# USB2_0_Connector.net
KiCad netlist of a schematic drawn in Altium Designer
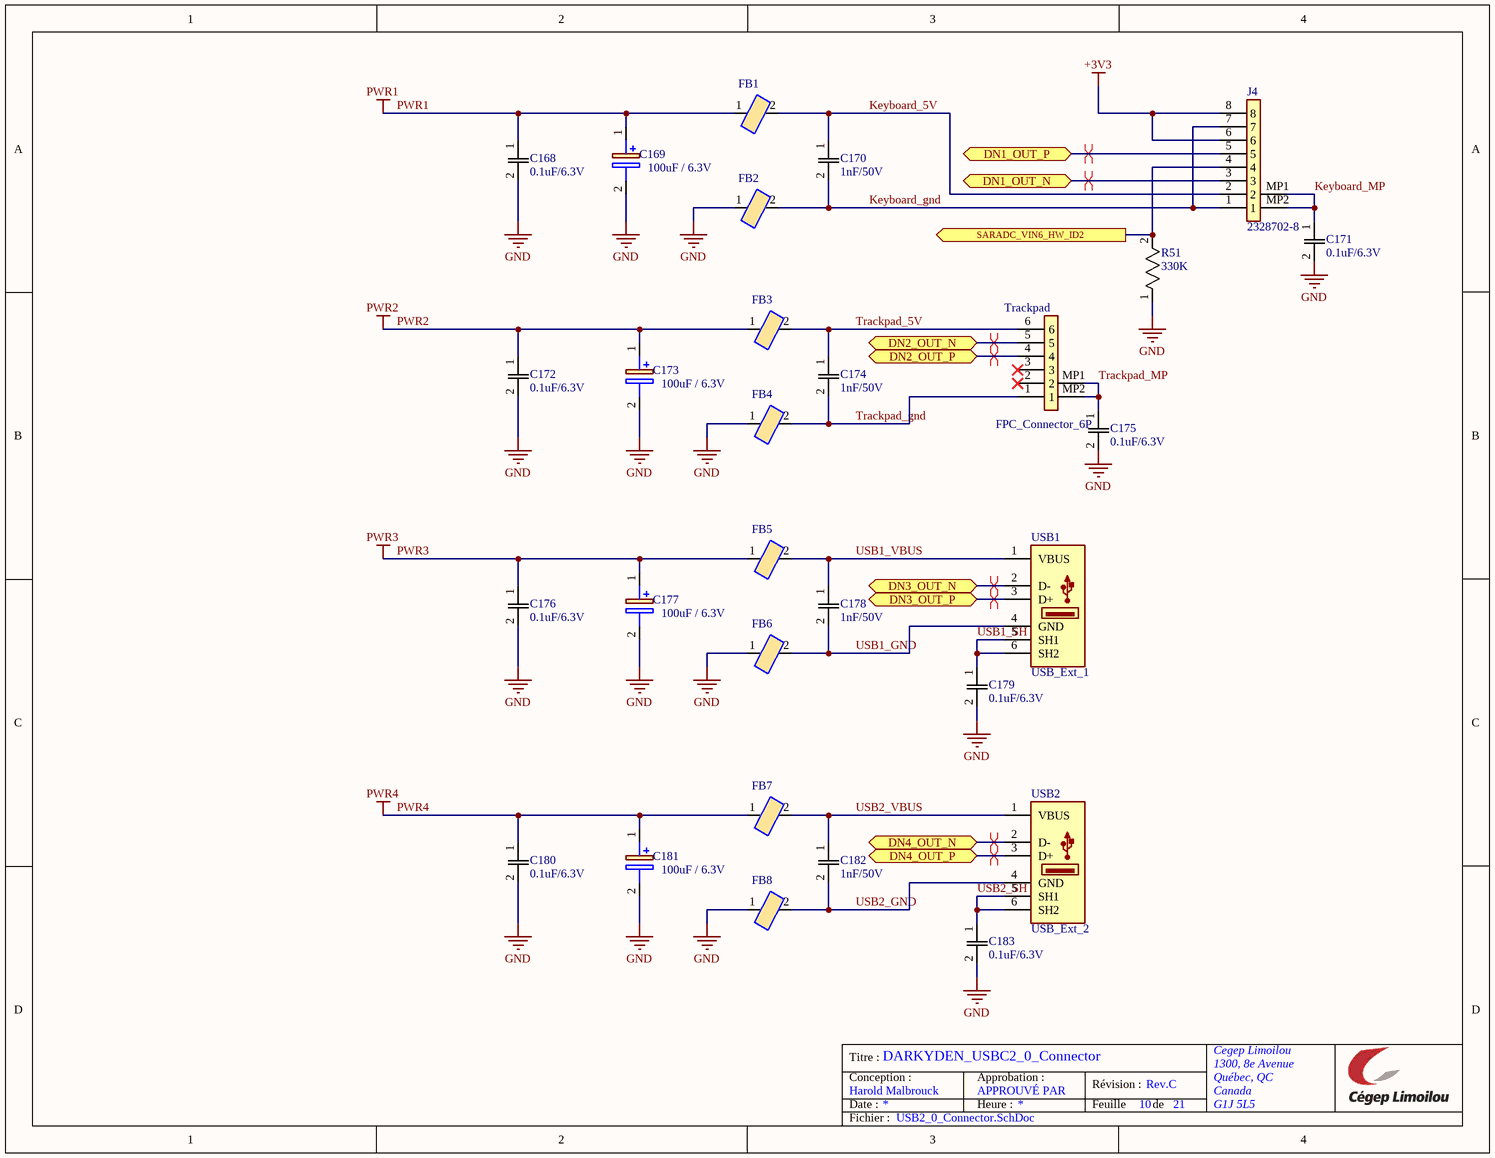
[diagram p0: USB2_0_Connector.SchDoc]

(export (version "E")
  (design (tool "Eeschema 10.0.6"))
  (components
    (comp (ref "C168")
      (value "0.1uF/6.3V")
      (footprint "C0805")
      (description "0.1uF 6.3V X7R 10% Pad SMD 0805 125C T/R")
      (fields
        (field (name "MOUSER PART NUMBER") "80-C0805C104K9R")
        (field (name "ARROW PART NUMBER") "C0805C104K9RACTU")
      )
      (libsource (lib "DARKYDEN") (part "C0805C104K9RACTU"))
    )
    (comp (ref "C169")
      (value "100uF / 6.3V")
      (footprint "SamacSys:EEE0GA101SR")
      (description "100uF 6.3V 20% Cap Aluminum Lytic  SMD 0.36 Ohm 240mA 2000h 105C Automotive T/R")
      (fields
        (field (name "MOUSER PART NUMBER") "667-EEE-FPJ101UAR")
        (field (name "ARROW PART NUMBER") "EEE-FPJ101UAR")
      )
      (libsource (lib "SamacSys") (part "EEE-FPJ101UAR"))
    )
    (comp (ref "C170")
      (value "1nF/50V")
      (footprint "C0805")
      (description "Multilayer Ceramic Capacitor 1000 Pf 50 V ½ 10% X7R 0805 [2012 Metric]")
      (fields
        (field (name "MANUFACTURER") "KEMET")
        (field (name "MANUFACTURER PART NUMBER") "C0805C102K5RACTU")
      )
      (libsource (lib "DARKYDEN") (part "C0805C102K5RACTU"))
    )
    (comp (ref "C171")
      (value "0.1uF/6.3V")
      (footprint "C0805")
      (description "0.1uF 6.3V X7R 10% Pad SMD 0805 125C T/R")
      (fields
        (field (name "MOUSER PART NUMBER") "80-C0805C104K9R")
        (field (name "ARROW PART NUMBER") "C0805C104K9RACTU")
      )
      (libsource (lib "DARKYDEN") (part "C0805C104K9RACTU"))
    )
    (comp (ref "C172")
      (value "0.1uF/6.3V")
      (footprint "C0805")
      (description "0.1uF 6.3V X7R 10% Pad SMD 0805 125C T/R")
      (fields
        (field (name "MOUSER PART NUMBER") "80-C0805C104K9R")
        (field (name "ARROW PART NUMBER") "C0805C104K9RACTU")
      )
      (libsource (lib "DARKYDEN") (part "C0805C104K9RACTU"))
    )
    (comp (ref "C173")
      (value "100uF / 6.3V")
      (footprint "SamacSys:EEE0GA101SR")
      (description "100uF 6.3V 20% Cap Aluminum Lytic  SMD 0.36 Ohm 240mA 2000h 105C Automotive T/R")
      (fields
        (field (name "MOUSER PART NUMBER") "667-EEE-FPJ101UAR")
        (field (name "ARROW PART NUMBER") "EEE-FPJ101UAR")
      )
      (libsource (lib "SamacSys") (part "EEE-FPJ101UAR"))
    )
    (comp (ref "C174")
      (value "1nF/50V")
      (footprint "C0805")
      (description "Multilayer Ceramic Capacitor 1000 Pf 50 V ½ 10% X7R 0805 [2012 Metric]")
      (fields
        (field (name "MANUFACTURER") "KEMET")
        (field (name "MANUFACTURER PART NUMBER") "C0805C102K5RACTU")
      )
      (libsource (lib "DARKYDEN") (part "C0805C102K5RACTU"))
    )
    (comp (ref "C175")
      (value "0.1uF/6.3V")
      (footprint "C0805")
      (description "0.1uF 6.3V X7R 10% Pad SMD 0805 125C T/R")
      (fields
        (field (name "MOUSER PART NUMBER") "80-C0805C104K9R")
        (field (name "ARROW PART NUMBER") "C0805C104K9RACTU")
      )
      (libsource (lib "DARKYDEN") (part "C0805C104K9RACTU"))
    )
    (comp (ref "C176")
      (value "0.1uF/6.3V")
      (footprint "C0805")
      (description "0.1uF 6.3V X7R 10% Pad SMD 0805 125C T/R")
      (fields
        (field (name "MOUSER PART NUMBER") "80-C0805C104K9R")
        (field (name "ARROW PART NUMBER") "C0805C104K9RACTU")
      )
      (libsource (lib "DARKYDEN") (part "C0805C104K9RACTU"))
    )
    (comp (ref "C177")
      (value "100uF / 6.3V")
      (footprint "SamacSys:EEE0GA101SR")
      (description "100uF 6.3V 20% Cap Aluminum Lytic  SMD 0.36 Ohm 240mA 2000h 105C Automotive T/R")
      (fields
        (field (name "MOUSER PART NUMBER") "667-EEE-FPJ101UAR")
        (field (name "ARROW PART NUMBER") "EEE-FPJ101UAR")
      )
      (libsource (lib "SamacSys") (part "EEE-FPJ101UAR"))
    )
    (comp (ref "C178")
      (value "1nF/50V")
      (footprint "C0805")
      (description "Multilayer Ceramic Capacitor 1000 Pf 50 V ½ 10% X7R 0805 [2012 Metric]")
      (fields
        (field (name "MANUFACTURER") "KEMET")
        (field (name "MANUFACTURER PART NUMBER") "C0805C102K5RACTU")
      )
      (libsource (lib "DARKYDEN") (part "C0805C102K5RACTU"))
    )
    (comp (ref "C179")
      (value "0.1uF/6.3V")
      (footprint "C0805")
      (description "0.1uF 6.3V X7R 10% Pad SMD 0805 125C T/R")
      (fields
        (field (name "MOUSER PART NUMBER") "80-C0805C104K9R")
        (field (name "ARROW PART NUMBER") "C0805C104K9RACTU")
      )
      (libsource (lib "DARKYDEN") (part "C0805C104K9RACTU"))
    )
    (comp (ref "C180")
      (value "0.1uF/6.3V")
      (footprint "C0805")
      (description "0.1uF 6.3V X7R 10% Pad SMD 0805 125C T/R")
      (fields
        (field (name "MOUSER PART NUMBER") "80-C0805C104K9R")
        (field (name "ARROW PART NUMBER") "C0805C104K9RACTU")
      )
      (libsource (lib "DARKYDEN") (part "C0805C104K9RACTU"))
    )
    (comp (ref "C181")
      (value "100uF / 6.3V")
      (footprint "SamacSys:EEE0GA101SR")
      (description "100uF 6.3V 20% Cap Aluminum Lytic  SMD 0.36 Ohm 240mA 2000h 105C Automotive T/R")
      (fields
        (field (name "MOUSER PART NUMBER") "667-EEE-FPJ101UAR")
        (field (name "ARROW PART NUMBER") "EEE-FPJ101UAR")
      )
      (libsource (lib "SamacSys") (part "EEE-FPJ101UAR"))
    )
    (comp (ref "C182")
      (value "1nF/50V")
      (footprint "C0805")
      (description "Multilayer Ceramic Capacitor 1000 Pf 50 V ½ 10% X7R 0805 [2012 Metric]")
      (fields
        (field (name "MANUFACTURER") "KEMET")
        (field (name "MANUFACTURER PART NUMBER") "C0805C102K5RACTU")
      )
      (libsource (lib "DARKYDEN") (part "C0805C102K5RACTU"))
    )
    (comp (ref "C183")
      (value "0.1uF/6.3V")
      (footprint "C0805")
      (description "0.1uF 6.3V X7R 10% Pad SMD 0805 125C T/R")
      (fields
        (field (name "MOUSER PART NUMBER") "80-C0805C104K9R")
        (field (name "ARROW PART NUMBER") "C0805C104K9RACTU")
      )
      (libsource (lib "DARKYDEN") (part "C0805C104K9RACTU"))
    )
    (comp (ref "FB1")
      (value "220R / 100MHz")
      (footprint "SamacSys:BLM18SP221SN1B")
      (description "Ferrite Beads Multi-Layer 220Ohm 25% 100MHz 2A 50mOhm DCR 0603 Paper T/R")
      (fields
        (field (name "MOUSER PART NUMBER") "81-BLM18EG221SN1D")
        (field (name "ARROW PART NUMBER") "BLM18EG221SN1D")
      )
      (libsource (lib "SamacSys") (part "BLM18EG221SN1D"))
    )
    (comp (ref "FB2")
      (value "220R / 100MHz")
      (footprint "SamacSys:BLM18SP221SN1B")
      (description "Ferrite Beads Multi-Layer 220Ohm 25% 100MHz 2A 50mOhm DCR 0603 Paper T/R")
      (fields
        (field (name "MOUSER PART NUMBER") "81-BLM18EG221SN1D")
        (field (name "ARROW PART NUMBER") "BLM18EG221SN1D")
      )
      (libsource (lib "SamacSys") (part "BLM18EG221SN1D"))
    )
    (comp (ref "FB3")
      (value "220R / 100MHz")
      (footprint "SamacSys:BLM18SP221SN1B")
      (description "Ferrite Beads Multi-Layer 220Ohm 25% 100MHz 2A 50mOhm DCR 0603 Paper T/R")
      (fields
        (field (name "MOUSER PART NUMBER") "81-BLM18EG221SN1D")
        (field (name "ARROW PART NUMBER") "BLM18EG221SN1D")
      )
      (libsource (lib "SamacSys") (part "BLM18EG221SN1D"))
    )
    (comp (ref "FB4")
      (value "220R / 100MHz")
      (footprint "SamacSys:BLM18SP221SN1B")
      (description "Ferrite Beads Multi-Layer 220Ohm 25% 100MHz 2A 50mOhm DCR 0603 Paper T/R")
      (fields
        (field (name "MOUSER PART NUMBER") "81-BLM18EG221SN1D")
        (field (name "ARROW PART NUMBER") "BLM18EG221SN1D")
      )
      (libsource (lib "SamacSys") (part "BLM18EG221SN1D"))
    )
    (comp (ref "FB5")
      (value "220R / 100MHz")
      (footprint "SamacSys:BLM18SP221SN1B")
      (description "Ferrite Beads Multi-Layer 220Ohm 25% 100MHz 2A 50mOhm DCR 0603 Paper T/R")
      (fields
        (field (name "MOUSER PART NUMBER") "81-BLM18EG221SN1D")
        (field (name "ARROW PART NUMBER") "BLM18EG221SN1D")
      )
      (libsource (lib "SamacSys") (part "BLM18EG221SN1D"))
    )
    (comp (ref "FB6")
      (value "220R / 100MHz")
      (footprint "SamacSys:BLM18SP221SN1B")
      (description "Ferrite Beads Multi-Layer 220Ohm 25% 100MHz 2A 50mOhm DCR 0603 Paper T/R")
      (fields
        (field (name "MOUSER PART NUMBER") "81-BLM18EG221SN1D")
        (field (name "ARROW PART NUMBER") "BLM18EG221SN1D")
      )
      (libsource (lib "SamacSys") (part "BLM18EG221SN1D"))
    )
    (comp (ref "FB7")
      (value "220R / 100MHz")
      (footprint "SamacSys:BLM18SP221SN1B")
      (description "Ferrite Beads Multi-Layer 220Ohm 25% 100MHz 2A 50mOhm DCR 0603 Paper T/R")
      (fields
        (field (name "MOUSER PART NUMBER") "81-BLM18EG221SN1D")
        (field (name "ARROW PART NUMBER") "BLM18EG221SN1D")
      )
      (libsource (lib "SamacSys") (part "BLM18EG221SN1D"))
    )
    (comp (ref "FB8")
      (value "220R / 100MHz")
      (footprint "SamacSys:BLM18SP221SN1B")
      (description "Ferrite Beads Multi-Layer 220Ohm 25% 100MHz 2A 50mOhm DCR 0603 Paper T/R")
      (fields
        (field (name "MOUSER PART NUMBER") "81-BLM18EG221SN1D")
        (field (name "ARROW PART NUMBER") "BLM18EG221SN1D")
      )
      (libsource (lib "SamacSys") (part "BLM18EG221SN1D"))
    )
    (comp (ref "J4")
      (value "2328702-8")
      (footprint "SamacSys:23287028")
      (description "Connector")
      (fields (field (name "MOUSER PART NUMBER") "571-2328702-8"))
      (libsource (lib "DARKYDEN") (part "2328702-8"))
    )
    (comp (ref "R51")
      (value "330K")
      (footprint "RESC1608X55N")
      (description "330 kOhm, ± 5%, 100 mW, 0603 [1608 Metric], Thick Film, General Purpose")
      (fields
        (field (name "MANUFACTURER") "Panasonic")
        (field (name "MANUFACTURER PART NUMBER") "ERJ-3GEYJ334V")
      )
      (libsource (lib "DARKYDEN") (part "ERJ-3GEYJ334V"))
    )
    (comp (ref "Trackpad")
      (value "FPC_Connector_6P")
      (footprint "SamacSys:23287026")
      (description "FPC Connector; 0.5mm pitch dual contact back flip FPC, 6pos ¦ TE Connectivity 2328702-6")
      (fields
        (field (name "MOUSER PART NUMBER") "571-2328702-6")
        (field (name "ARROW PART NUMBER") "2328702-6")
      )
      (libsource (lib "SamacSys") (part "2328702-6"))
    )
    (comp (ref "USB1")
      (value "USB_Ext_1")
      (footprint "SamacSys:TECONN-4POS-USB")
      (description "USB-A (USB TYPE-A) USB 2.0 Receptacle Connector 4 Position Through Hole, Right Angle")
      (fields
        (field (name "MOUSER PART NUMBER") "571-292303-1")
        (field (name "ARROW PART NUMBER") "292303-1")
      )
      (libsource (lib "SamacSys") (part "292303-1"))
    )
    (comp (ref "USB2")
      (value "USB_Ext_2")
      (footprint "SamacSys:TECONN-4POS-USB")
      (description "USB-A (USB TYPE-A) USB 2.0 Receptacle Connector 4 Position Through Hole, Right Angle")
      (fields
        (field (name "MOUSER PART NUMBER") "571-292303-1")
        (field (name "ARROW PART NUMBER") "292303-1")
      )
      (libsource (lib "SamacSys") (part "292303-1"))
    )
  )
  (nets
    (net (code "1") (name "+3V3") (class "Default")
      (node (ref "J4") (pin "6") (pinfunction "6_6") (pintype "passive"))
      (node (ref "J4") (pin "8") (pinfunction "8_8") (pintype "passive"))
    )
    (net (code "2") (name "/DN1_OUT_N") (class "Default")
      (node (ref "J4") (pin "3") (pinfunction "3_3") (pintype "passive"))
    )
    (net (code "3") (name "/DN1_OUT_P") (class "Default")
      (node (ref "J4") (pin "5") (pinfunction "5_5") (pintype "passive"))
    )
    (net (code "4") (name "/DN2_OUT_N") (class "Default")
      (node (ref "Trackpad") (pin "5") (pinfunction "5_5") (pintype "passive"))
    )
    (net (code "5") (name "/DN2_OUT_P") (class "Default")
      (node (ref "Trackpad") (pin "4") (pinfunction "4_4") (pintype "passive"))
    )
    (net (code "6") (name "/DN3_OUT_N") (class "Default")
      (node (ref "USB1") (pin "2") (pinfunction "D-_2") (pintype "passive"))
    )
    (net (code "7") (name "/DN3_OUT_P") (class "Default")
      (node (ref "USB1") (pin "3") (pinfunction "D+_3") (pintype "passive"))
    )
    (net (code "8") (name "/DN4_OUT_N") (class "Default")
      (node (ref "USB2") (pin "2") (pinfunction "D-_2") (pintype "passive"))
    )
    (net (code "9") (name "/DN4_OUT_P") (class "Default")
      (node (ref "USB2") (pin "3") (pinfunction "D+_3") (pintype "passive"))
    )
    (net (code "10") (name "/Keyboard_5V") (class "Default")
      (node (ref "C170") (pin "1") (pinfunction "1_1") (pintype "passive"))
      (node (ref "FB1") (pin "2") (pinfunction "2_2") (pintype "passive"))
      (node (ref "J4") (pin "2") (pinfunction "2_2") (pintype "passive"))
    )
    (net (code "11") (name "/Keyboard_MP") (class "Default")
      (node (ref "C171") (pin "1") (pinfunction "1_1") (pintype "passive"))
      (node (ref "J4") (pin "MP1") (pinfunction "MP1_MP1") (pintype "passive"))
      (node (ref "J4") (pin "MP2") (pinfunction "MP2_MP2") (pintype "passive"))
    )
    (net (code "12") (name "/Keyboard_gnd") (class "Default")
      (node (ref "C170") (pin "2") (pinfunction "2_2") (pintype "passive"))
      (node (ref "FB2") (pin "2") (pinfunction "2_2") (pintype "passive"))
      (node (ref "J4") (pin "1") (pinfunction "1_1") (pintype "passive"))
      (node (ref "J4") (pin "7") (pinfunction "7_7") (pintype "passive"))
    )
    (net (code "13") (name "/SARADC_VIN6_HW_ID2") (class "Default")
      (node (ref "J4") (pin "4") (pinfunction "4_4") (pintype "passive"))
      (node (ref "R51") (pin "2") (pinfunction "2_2") (pintype "passive"))
    )
    (net (code "14") (name "/Trackpad_5V") (class "Default")
      (node (ref "C174") (pin "1") (pinfunction "1_1") (pintype "passive"))
      (node (ref "FB3") (pin "2") (pinfunction "2_2") (pintype "passive"))
      (node (ref "Trackpad") (pin "6") (pinfunction "6_6") (pintype "passive"))
    )
    (net (code "15") (name "/Trackpad_MP") (class "Default")
      (node (ref "C175") (pin "1") (pinfunction "1_1") (pintype "passive"))
      (node (ref "Trackpad") (pin "MP1") (pinfunction "MP1_MP1") (pintype "passive"))
      (node (ref "Trackpad") (pin "MP2") (pinfunction "MP2_MP2") (pintype "passive"))
    )
    (net (code "16") (name "/Trackpad_gnd") (class "Default")
      (node (ref "C174") (pin "2") (pinfunction "2_2") (pintype "passive"))
      (node (ref "FB4") (pin "2") (pinfunction "2_2") (pintype "passive"))
      (node (ref "Trackpad") (pin "1") (pinfunction "1_1") (pintype "passive"))
    )
    (net (code "17") (name "/USB1_GND") (class "Default")
      (node (ref "C178") (pin "2") (pinfunction "2_2") (pintype "passive"))
      (node (ref "FB6") (pin "2") (pinfunction "2_2") (pintype "passive"))
      (node (ref "USB1") (pin "4") (pinfunction "GND_4") (pintype "passive"))
    )
    (net (code "18") (name "/USB1_SH") (class "Default")
      (node (ref "C179") (pin "1") (pinfunction "1_1") (pintype "passive"))
      (node (ref "USB1") (pin "5") (pinfunction "SH1_5") (pintype "passive"))
      (node (ref "USB1") (pin "6") (pinfunction "SH2_6") (pintype "passive"))
    )
    (net (code "19") (name "/USB1_VBUS") (class "Default")
      (node (ref "C178") (pin "1") (pinfunction "1_1") (pintype "passive"))
      (node (ref "FB5") (pin "2") (pinfunction "2_2") (pintype "passive"))
      (node (ref "USB1") (pin "1") (pinfunction "VBUS_1") (pintype "passive"))
    )
    (net (code "20") (name "/USB2_GND") (class "Default")
      (node (ref "C182") (pin "2") (pinfunction "2_2") (pintype "passive"))
      (node (ref "FB8") (pin "2") (pinfunction "2_2") (pintype "passive"))
      (node (ref "USB2") (pin "4") (pinfunction "GND_4") (pintype "passive"))
    )
    (net (code "21") (name "/USB2_SH") (class "Default")
      (node (ref "C183") (pin "1") (pinfunction "1_1") (pintype "passive"))
      (node (ref "USB2") (pin "5") (pinfunction "SH1_5") (pintype "passive"))
      (node (ref "USB2") (pin "6") (pinfunction "SH2_6") (pintype "passive"))
    )
    (net (code "22") (name "/USB2_VBUS") (class "Default")
      (node (ref "C182") (pin "1") (pinfunction "1_1") (pintype "passive"))
      (node (ref "FB7") (pin "2") (pinfunction "2_2") (pintype "passive"))
      (node (ref "USB2") (pin "1") (pinfunction "VBUS_1") (pintype "passive"))
    )
    (net (code "23") (name "GND") (class "Default")
      (node (ref "C168") (pin "2") (pinfunction "2_2") (pintype "passive"))
      (node (ref "C169") (pin "2") (pinfunction "-_2") (pintype "passive"))
      (node (ref "C171") (pin "2") (pinfunction "2_2") (pintype "passive"))
      (node (ref "C172") (pin "2") (pinfunction "2_2") (pintype "passive"))
      (node (ref "C173") (pin "2") (pinfunction "-_2") (pintype "passive"))
      (node (ref "C175") (pin "2") (pinfunction "2_2") (pintype "passive"))
      (node (ref "C176") (pin "2") (pinfunction "2_2") (pintype "passive"))
      (node (ref "C177") (pin "2") (pinfunction "-_2") (pintype "passive"))
      (node (ref "C179") (pin "2") (pinfunction "2_2") (pintype "passive"))
      (node (ref "C180") (pin "2") (pinfunction "2_2") (pintype "passive"))
      (node (ref "C181") (pin "2") (pinfunction "-_2") (pintype "passive"))
      (node (ref "C183") (pin "2") (pinfunction "2_2") (pintype "passive"))
      (node (ref "FB2") (pin "1") (pinfunction "1_1") (pintype "passive"))
      (node (ref "FB4") (pin "1") (pinfunction "1_1") (pintype "passive"))
      (node (ref "FB6") (pin "1") (pinfunction "1_1") (pintype "passive"))
      (node (ref "FB8") (pin "1") (pinfunction "1_1") (pintype "passive"))
      (node (ref "R51") (pin "1") (pinfunction "1_1") (pintype "passive"))
    )
    (net (code "24") (name "PWR1") (class "Default")
      (node (ref "C168") (pin "1") (pinfunction "1_1") (pintype "passive"))
      (node (ref "C169") (pin "1") (pinfunction "+_1") (pintype "passive"))
      (node (ref "FB1") (pin "1") (pinfunction "1_1") (pintype "passive"))
    )
    (net (code "25") (name "PWR2") (class "Default")
      (node (ref "C172") (pin "1") (pinfunction "1_1") (pintype "passive"))
      (node (ref "C173") (pin "1") (pinfunction "+_1") (pintype "passive"))
      (node (ref "FB3") (pin "1") (pinfunction "1_1") (pintype "passive"))
    )
    (net (code "26") (name "PWR3") (class "Default")
      (node (ref "C176") (pin "1") (pinfunction "1_1") (pintype "passive"))
      (node (ref "C177") (pin "1") (pinfunction "+_1") (pintype "passive"))
      (node (ref "FB5") (pin "1") (pinfunction "1_1") (pintype "passive"))
    )
    (net (code "27") (name "PWR4") (class "Default")
      (node (ref "C180") (pin "1") (pinfunction "1_1") (pintype "passive"))
      (node (ref "C181") (pin "1") (pinfunction "+_1") (pintype "passive"))
      (node (ref "FB7") (pin "1") (pinfunction "1_1") (pintype "passive"))
    )
    (net (code "28") (name "unconnected-(Trackpad-Pad2)") (class "Default")
      (node (ref "Trackpad") (pin "2") (pinfunction "2_2") (pintype "passive+no_connect"))
    )
    (net (code "29") (name "unconnected-(Trackpad-Pad3)") (class "Default")
      (node (ref "Trackpad") (pin "3") (pinfunction "3_3") (pintype "passive+no_connect"))
    )
  )
)
